# KickTrigger.net
KiCad netlist of a schematic drawn in Altium Designer
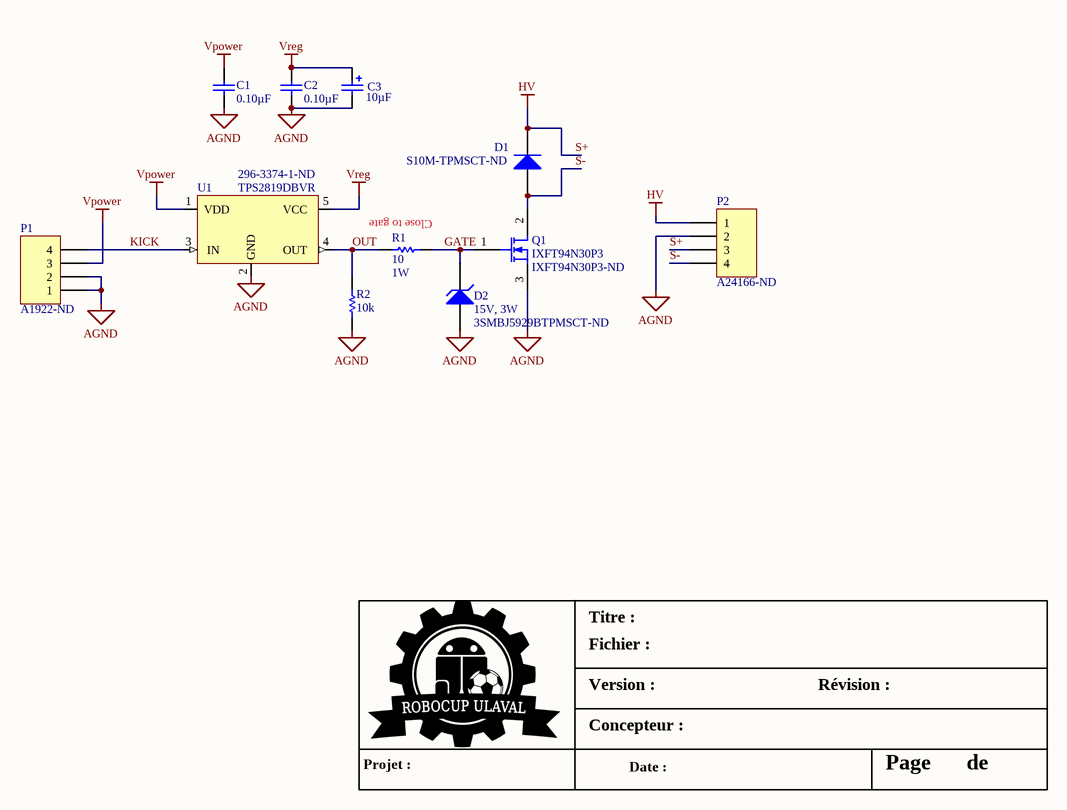
[diagram p0: KickTrigger.SchDoc]

(export (version "E")
  (design (tool "Eeschema 10.0.6"))
  (components
    (comp (ref "C1")
      (value "CL10B104KB8SFNC")
      (footprint "0603")
      (description "CAP CER 0.1UF 50V X7R 0603")
      (fields
        (field (name "MANUFACTURER") "Samsung Electro-Mechanics America, Inc.")
        (field (name "TOLERANCE") "±10%")
        (field (name "CAPACITANCE") "0.10µF")
      )
      (libsource (lib "ResCap") (part "CL10B104KB8SFNC"))
    )
    (comp (ref "C2")
      (value "CL10B104KB8SFNC")
      (footprint "0603")
      (description "CAP CER 0.1UF 50V X7R 0603")
      (fields
        (field (name "MANUFACTURER") "Samsung Electro-Mechanics America, Inc.")
        (field (name "TOLERANCE") "±10%")
        (field (name "CAPACITANCE") "0.10µF")
      )
      (libsource (lib "ResCap") (part "CL10B104KB8SFNC"))
    )
    (comp (ref "C3")
      (value "865230340001")
      (footprint "CAP 4.3x4.3mm")
      (description "CAP 10 UF 20% 16 V")
      (fields
        (field (name "MANUFACTURER") "Wurth Electronics Inc")
        (field (name "CAPACITANCE") "10µF")
        (field (name "TOLERANCE") "±20%")
      )
      (libsource (lib "ResCap") (part "865230340001"))
    )
    (comp (ref "D1")
      (value "S10M-TP")
      (footprint "HSMC")
      (description "DIODE GEN PURP 1KV 10A DO214AB")
      (fields
        (field (name "MANUFACTURER") "Micro Commercial Co")
        (field (name "SUPPLIER PART NUMBER 1") "S10M-TPMSCT-ND")
      )
      (libsource (lib "gamma_kicker") (part "S10M-TP"))
    )
    (comp (ref "D2")
      (value "15V, 3W")
      (footprint "SMB")
      (description "DIODE ZENER 15V 3W DO214AA")
      (fields
        (field (name "MANUFACTURER") "Micro Commercial Co")
        (field (name "MANUFACTURER PART NUMBER") "3SMBJ5929B-TP")
        (field (name "SUPPLIER PART NUMBER 1") "3SMBJ5929BTPMSCT-ND")
      )
      (libsource (lib "gamma_kicker") (part "3SMBJ5929B-TP"))
    )
    (comp (ref "P1")
      (value "header 4pin 0.100")
      (footprint "0.100MIL 4PIN HEADER")
      (description "CONN HEADER VERT 4POS .100 TIN")
      (fields
        (field (name "MANUFACTURER") "TE Connectivity AMP Connectors")
        (field (name "MANUFACTURER PART NUMBER") "640456-4")
        (field (name "SUPPLIER PART NUMBER 1") "A1922-ND")
      )
      (libsource (lib "gamma_kicker") (part "header 4pin 0.100"))
    )
    (comp (ref "P2")
      (value "Header 4pin 0.156")
      (footprint "0.156mil 4pin header")
      (description "CONN HEADER VERT 4POS .156 TIN")
      (fields (field (name "SUPPLIER PART NUMBER 1") "A24166-ND"))
      (libsource (lib "gamma_kicker") (part "Header 4pin 0.156"))
    )
    (comp (ref "Q1")
      (value "IXFT94N30P3")
      (footprint "TO-268")
      (description "MOSFET N-CH 300V 94A TO-268")
      (fields (field (name "MANUFACTURER") "IXYS") (field (name "SUPPLIER PART NUMBER 1") "IXFT94N30P3-ND"))
      (libsource (lib "gamma_kicker") (part "IXFT94N30P3"))
    )
    (comp (ref "R1")
      (value "RMCP2010FT10R0")
      (footprint "2010")
      (description "RES SMD 10 OHM 1% 1W 2010")
      (fields
        (field (name "MANUFACTURER") "Stackpole Electronics Inc.")
        (field (name "TOLERANCE") "±1%")
        (field (name "RESISTANCE (OHMS)") "10")
        (field (name "POWER (WATTS)") "1W")
      )
      (libsource (lib "ResCap") (part "RMCP2010FT10R0"))
    )
    (comp (ref "R2")
      (value "RC0603JR-0710KL")
      (footprint "0603")
      (description "RES SMD 10K OHM 5% 1/10W 0603")
      (fields
        (field (name "MANUFACTURER") "Yageo")
        (field (name "TOLERANCE") "±5%")
        (field (name "RESISTANCE (OHMS)") "10k")
      )
      (libsource (lib "ResCap") (part "RC0603JR-0710KL"))
    )
    (comp (ref "U1")
      (value "TPS2819DBVR")
      (footprint "SOT-23-5")
      (description "IC NONINVERT FET DRVR SOT-23-5")
      (fields
        (field (name "MANUFACTURER") "Texas Instruments")
        (field (name "SUPPLIER PART NUMBER 1") "296-3374-1-ND")
      )
      (libsource (lib "gamma_kicker") (part "TPS2819DBVR"))
    )
  )
  (nets
    (net (code "1") (name "/GATE") (class "Default")
      (node (ref "D2") (pin "K") (pinfunction "K_K") (pintype "passive"))
      (node (ref "Q1") (pin "1") (pinfunction "G_1") (pintype "passive"))
      (node (ref "R1") (pin "2") (pinfunction "2_2") (pintype "passive"))
    )
    (net (code "2") (name "/KICK") (class "Default")
      (node (ref "P1") (pin "4") (pinfunction "4_4") (pintype "passive"))
      (node (ref "U1") (pin "3") (pinfunction "IN_3") (pintype "input"))
    )
    (net (code "3") (name "/OUT") (class "Default")
      (node (ref "R1") (pin "1") (pinfunction "1_1") (pintype "passive"))
      (node (ref "R2") (pin "2") (pinfunction "2_2") (pintype "passive"))
      (node (ref "U1") (pin "4") (pinfunction "OUT_4") (pintype "output"))
    )
    (net (code "4") (name "/S-") (class "Default")
      (node (ref "D1") (pin "A") (pinfunction "A_A") (pintype "passive"))
      (node (ref "P2") (pin "4") (pinfunction "4_4") (pintype "passive"))
      (node (ref "Q1") (pin "2") (pinfunction "D_2") (pintype "passive"))
    )
    (net (code "5") (name "AGND") (class "Default")
      (node (ref "C1") (pin "1") (pinfunction "1_1") (pintype "passive"))
      (node (ref "C2") (pin "1") (pinfunction "1_1") (pintype "passive"))
      (node (ref "C3") (pin "2") (pinfunction "2_2") (pintype "passive"))
      (node (ref "D2") (pin "A") (pinfunction "A_A") (pintype "passive"))
      (node (ref "P1") (pin "1") (pinfunction "1_1") (pintype "passive"))
      (node (ref "P1") (pin "2") (pinfunction "2_2") (pintype "passive"))
      (node (ref "P2") (pin "2") (pinfunction "2_2") (pintype "passive"))
      (node (ref "Q1") (pin "3") (pinfunction "S_3") (pintype "passive"))
      (node (ref "R2") (pin "1") (pinfunction "1_1") (pintype "passive"))
      (node (ref "U1") (pin "2") (pinfunction "GND_2") (pintype "power_in"))
    )
    (net (code "6") (name "HV") (class "Default")
      (node (ref "D1") (pin "K") (pinfunction "K_K") (pintype "passive"))
      (node (ref "P2") (pin "1") (pinfunction "1_1") (pintype "passive"))
      (node (ref "P2") (pin "3") (pinfunction "3_3") (pintype "passive"))
    )
    (net (code "7") (name "Vpower") (class "Default")
      (node (ref "C1") (pin "2") (pinfunction "2_2") (pintype "passive"))
      (node (ref "P1") (pin "3") (pinfunction "3_3") (pintype "passive"))
      (node (ref "U1") (pin "1") (pinfunction "VDD_1") (pintype "power_in"))
    )
    (net (code "8") (name "Vreg") (class "Default")
      (node (ref "C2") (pin "2") (pinfunction "2_2") (pintype "passive"))
      (node (ref "C3") (pin "1") (pinfunction "1_1") (pintype "passive"))
      (node (ref "U1") (pin "5") (pinfunction "VCC_5") (pintype "power_in"))
    )
  )
)
